# badge.net
KiCad netlist of a schematic drawn in EAGLE
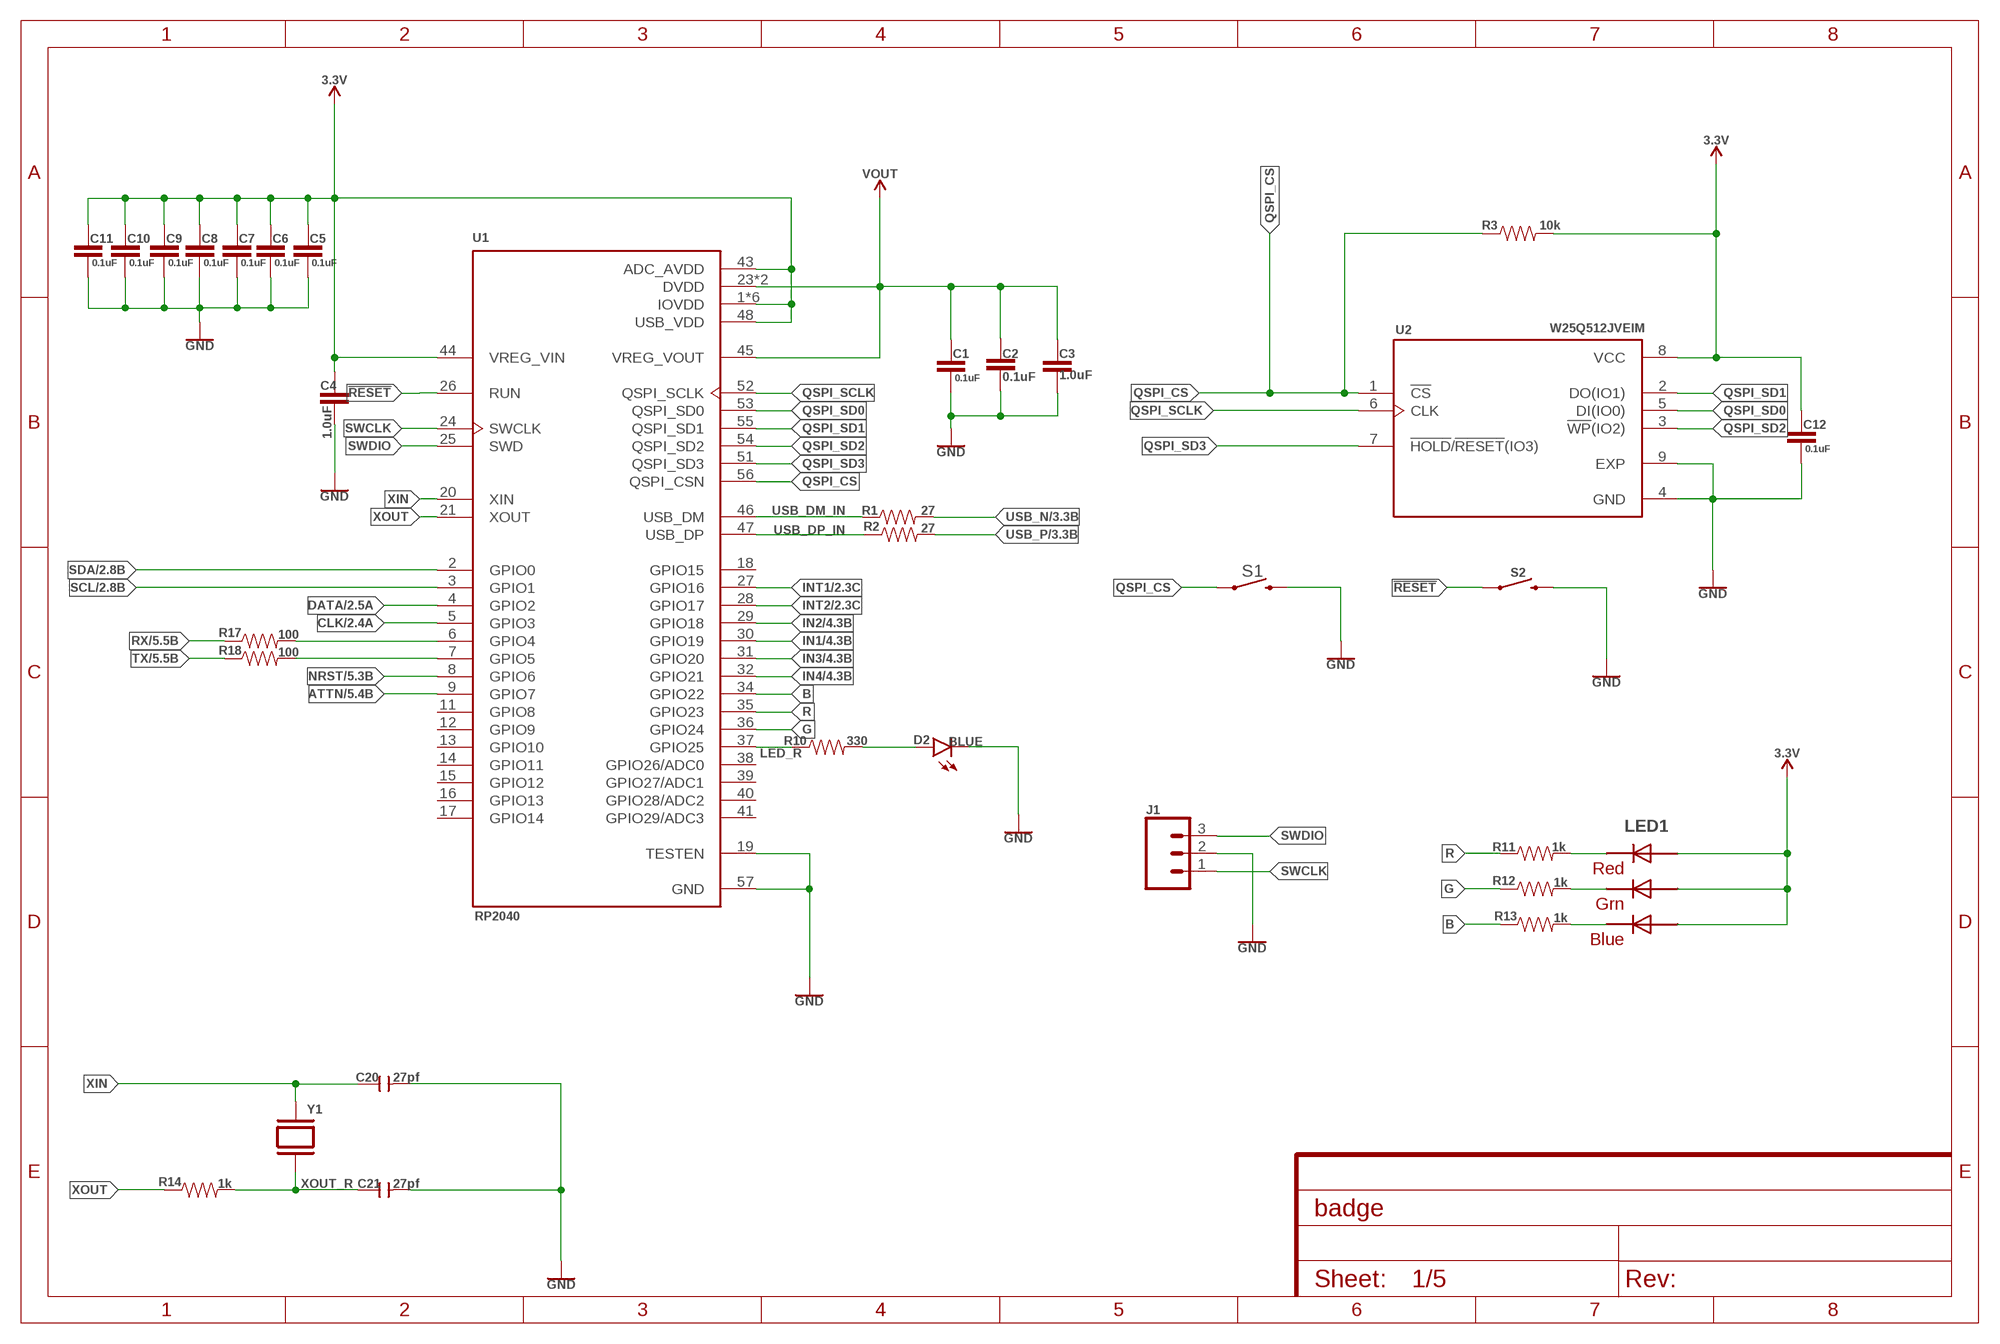
[diagram p0: schematic, sheet 1]
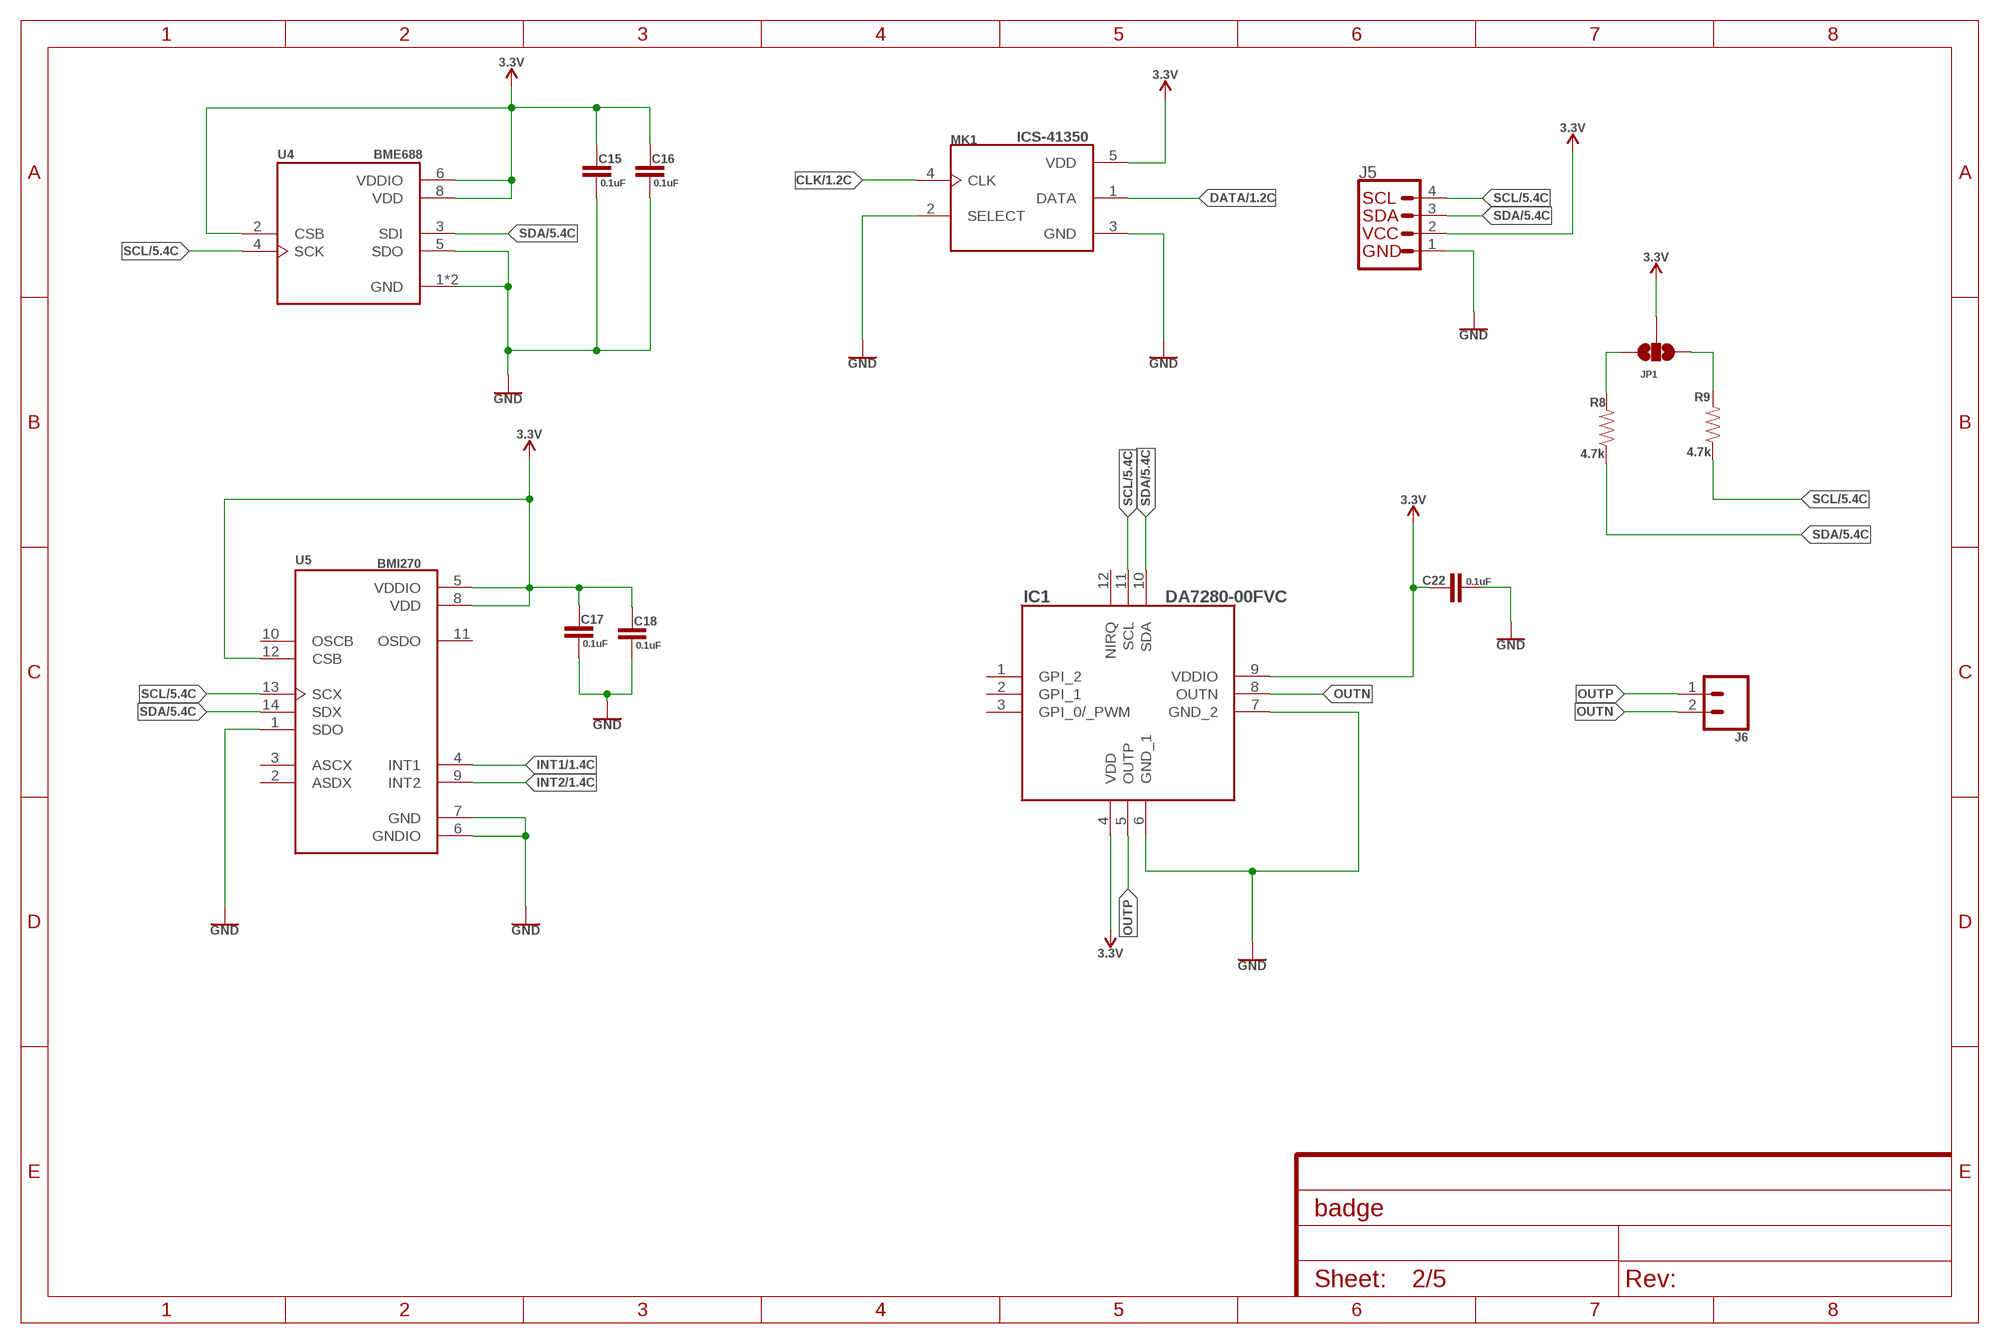
[diagram p1: schematic, sheet 2]
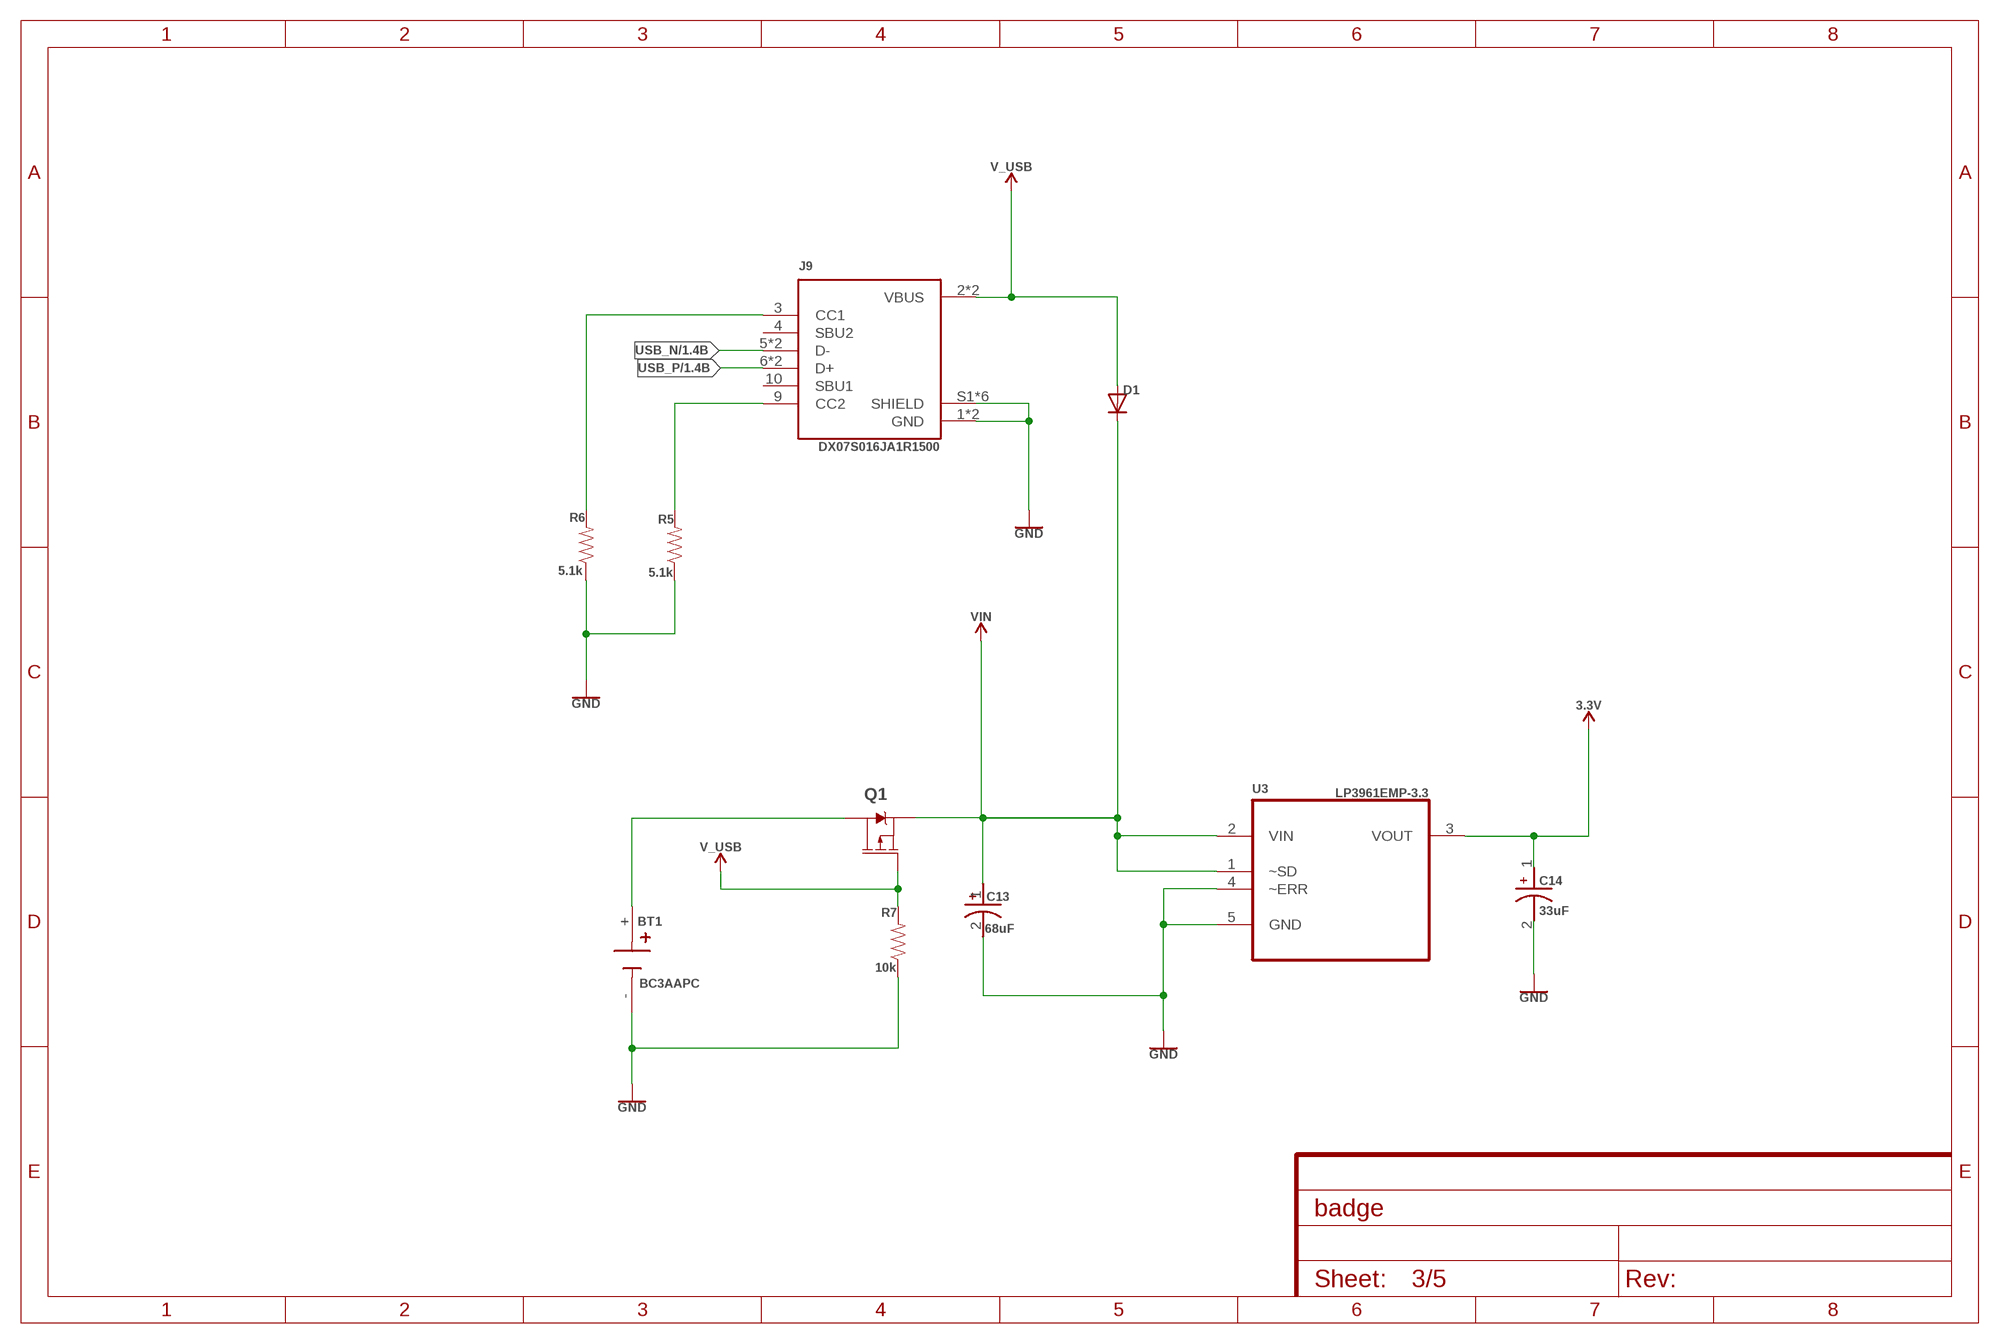
[diagram p2: schematic, sheet 3]
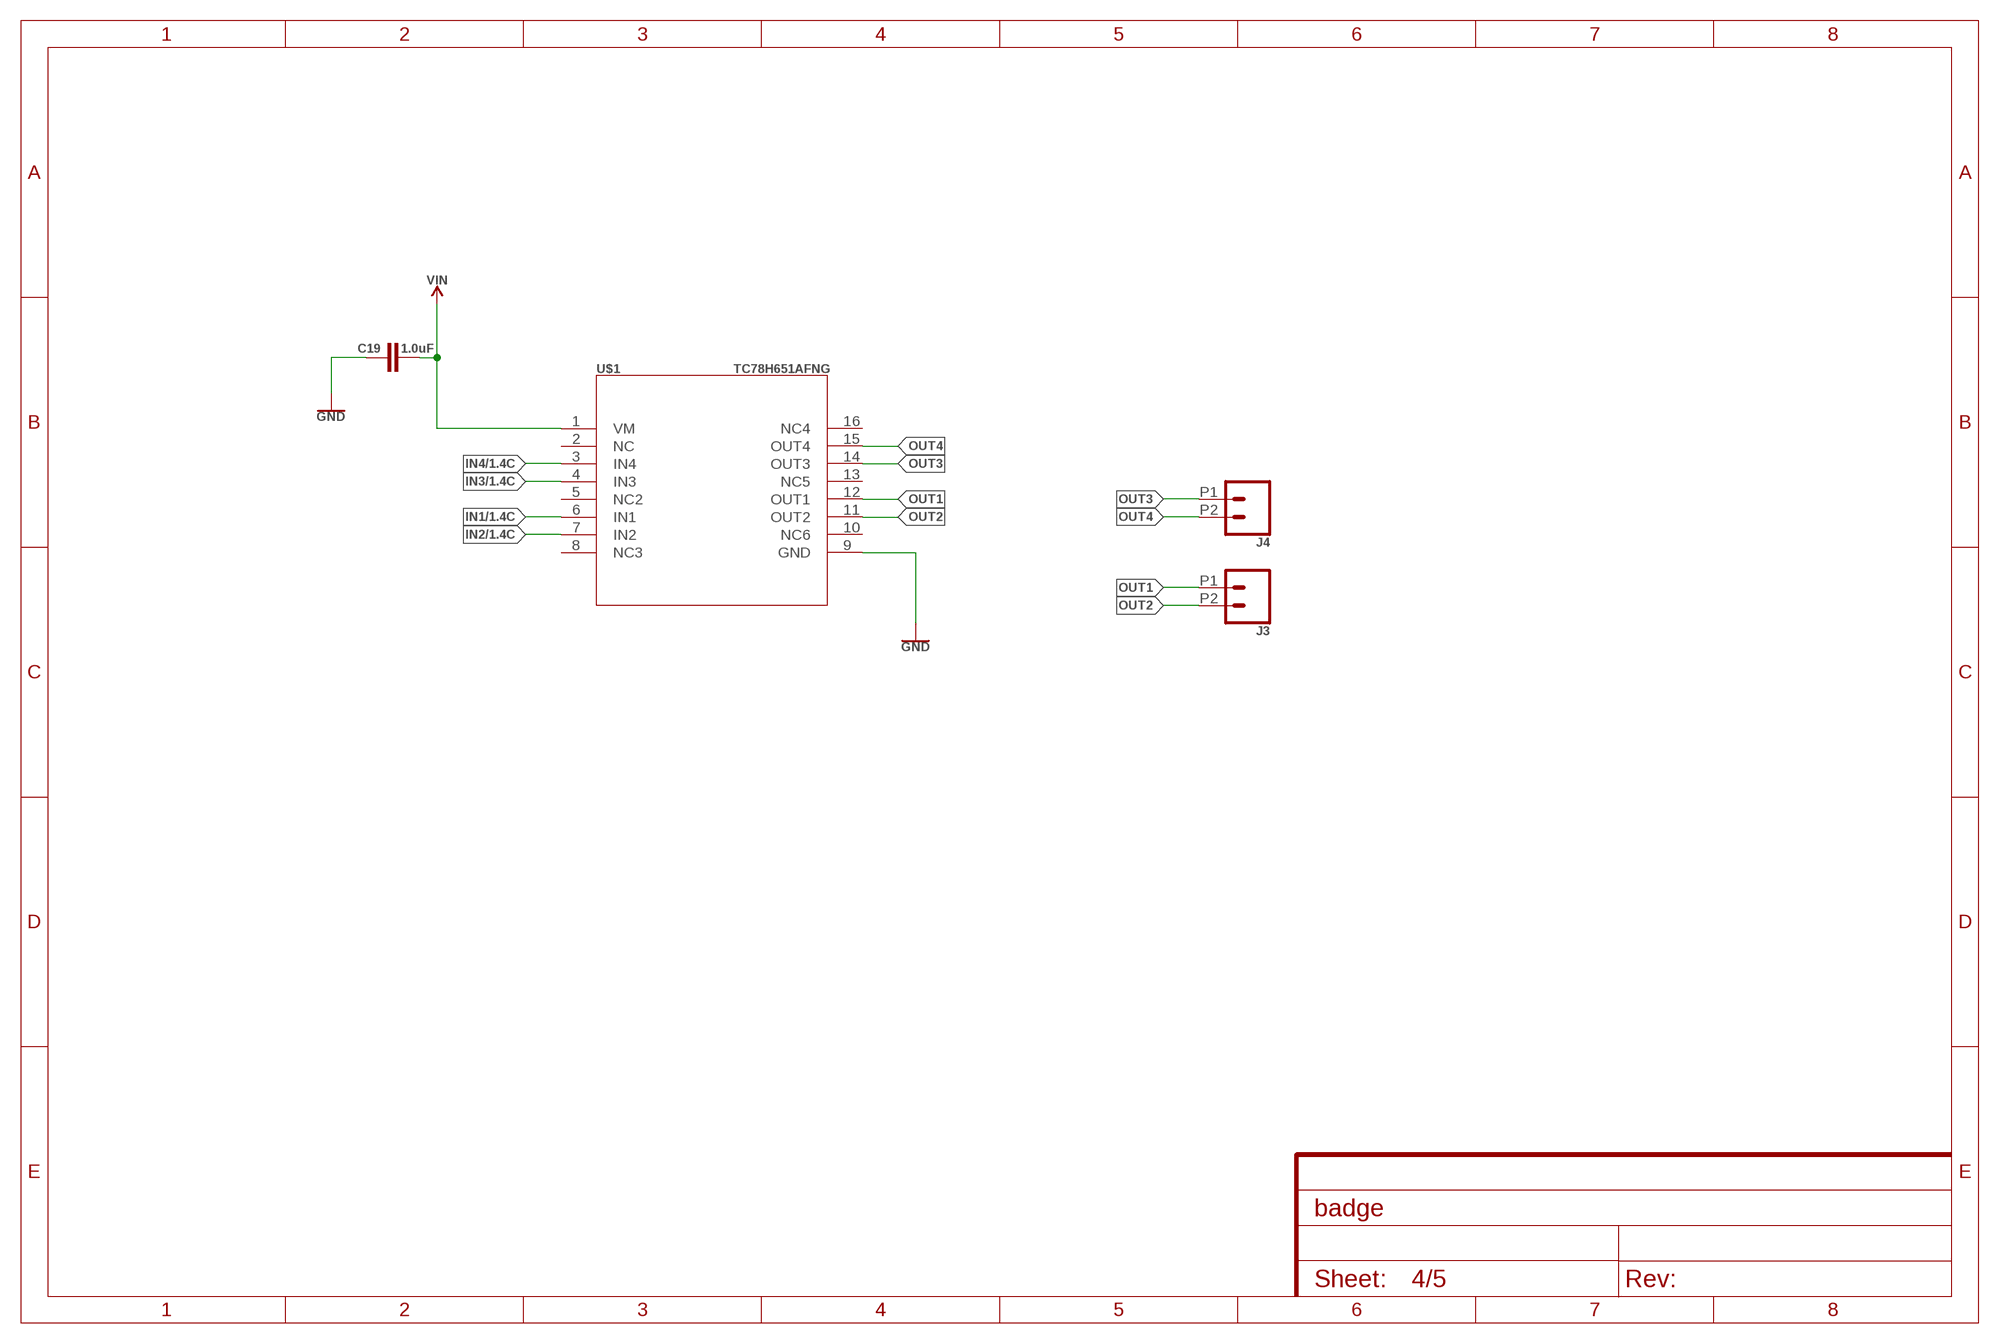
[diagram p3: schematic, sheet 4]
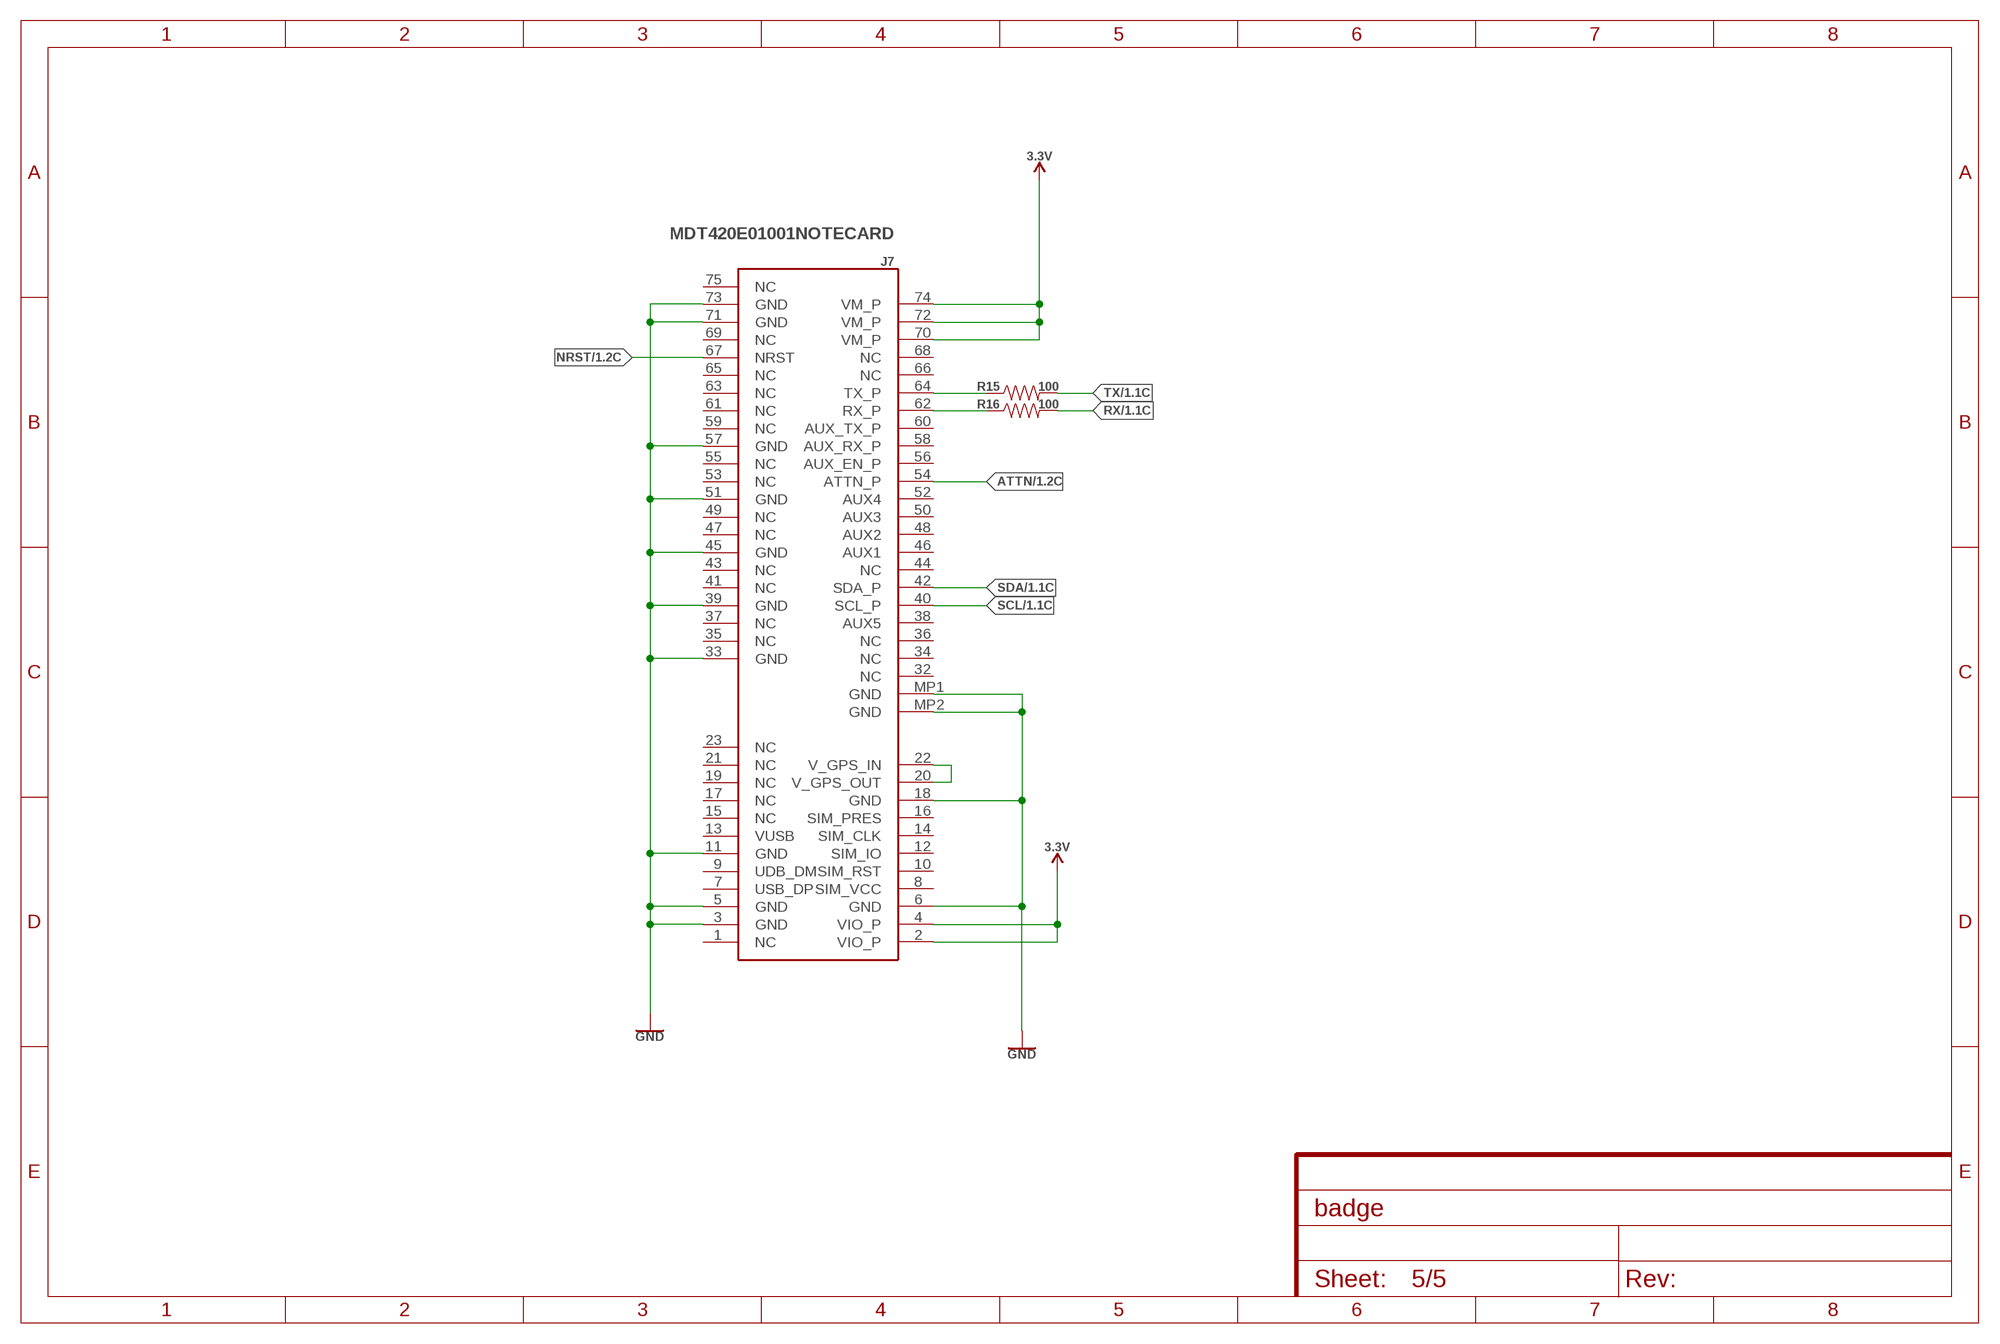
[diagram p4: schematic, sheet 5]

(export (version "E")
  (design (tool "Eeschema 10.0.6"))
  (components
    (comp (ref "BT1")
      (value "BC3AAPC")
      (footprint "eagle-import:BAT_BC3AAPC")
      (fields (field (name "MF") "MPD"))
      (libsource (lib "eagle-import") (part "BC3AAPC"))
    )
    (comp (ref "C13")
      (value "68uF")
      (footprint "eagle-import:CAPMP3216X180N")
      (fields (field (name "MF") "KEMET") (field (name "MP") "T491A686M006AT"))
      (libsource (lib "eagle-import") (part "T491A686M006AT"))
    )
    (comp (ref "C14")
      (value "33uF")
      (footprint "eagle-import:CAPMP3216X180N")
      (fields (field (name "MF") "AVX") (field (name "MP") "TAJA336K006RNJ"))
      (libsource (lib "eagle-import") (part "TAJA336K006RNJ"))
    )
    (comp (ref "D1")
      (value "DIODESOD-123")
      (footprint "eagle-import:SOD-123")
      (libsource (lib "eagle-import") (part "DIODESOD-123"))
    )
    (comp (ref "J9")
      (value "DX07S016JA1R1500")
      (footprint "eagle-import:JAE_DX07S016JA1R1500")
      (fields (field (name "MF") "JAE Electronics"))
      (libsource (lib "eagle-import") (part "DX07S016JA1R1500"))
    )
    (comp (ref "Q1")
      (value "2.5A/30V/105mΩ")
      (footprint "eagle-import:SOT23-3")
      (libsource (lib "eagle-import") (part "MOSFET_PCH-DMG2307L"))
    )
    (comp (ref "R5")
      (value "5.1k")
      (footprint "eagle-import:0603")
      (libsource (lib "eagle-import") (part "5.6KOHM-0603-1/10W-1%"))
    )
    (comp (ref "R6")
      (value "5.1k")
      (footprint "eagle-import:0603")
      (libsource (lib "eagle-import") (part "5.6KOHM-0603-1/10W-1%"))
    )
    (comp (ref "R7")
      (value "10k")
      (footprint "eagle-import:0603")
      (libsource (lib "eagle-import") (part "10KOHM-0603-1/10W-1%"))
    )
    (comp (ref "U3")
      (value "LP3961EMP-3.3")
      (footprint "eagle-import:SOT150P696X180-5N")
      (fields
        (field (name "DIGI-KEY_PART_NUMBER") "LP3961EMP-3.3/NOPBTR-ND")
        (field (name "MF") "Texas Instruments")
        (field (name "MP") "LP3961EMP-3.3/NOPB")
      )
      (libsource (lib "eagle-import") (part "LP3961EMP-3.3"))
    )
    (comp (ref "C1")
      (value "0.1uF")
      (footprint "eagle-import:0603")
      (libsource (lib "eagle-import") (part "0.1UF-0603-25V-(+80/-20%)"))
    )
    (comp (ref "C2")
      (value "0.1uF")
      (footprint "eagle-import:0603")
      (libsource (lib "eagle-import") (part "0.1UF-0603-25V-(+80/-20%)"))
    )
    (comp (ref "C3")
      (value "1.0uF")
      (footprint "eagle-import:0603")
      (libsource (lib "eagle-import") (part "1.0UF-0603-16V-10%"))
    )
    (comp (ref "C4")
      (value "1.0uF")
      (footprint "eagle-import:0603")
      (libsource (lib "eagle-import") (part "1.0UF-0603-16V-10%"))
    )
    (comp (ref "C5")
      (value "0.1uF")
      (footprint "eagle-import:0603")
      (libsource (lib "eagle-import") (part "0.1UF-0603-25V-(+80/-20%)"))
    )
    (comp (ref "C6")
      (value "0.1uF")
      (footprint "eagle-import:0603")
      (libsource (lib "eagle-import") (part "0.1UF-0603-25V-(+80/-20%)"))
    )
    (comp (ref "C7")
      (value "0.1uF")
      (footprint "eagle-import:0603")
      (libsource (lib "eagle-import") (part "0.1UF-0603-25V-(+80/-20%)"))
    )
    (comp (ref "C8")
      (value "0.1uF")
      (footprint "eagle-import:0603")
      (libsource (lib "eagle-import") (part "0.1UF-0603-25V-(+80/-20%)"))
    )
    (comp (ref "C9")
      (value "0.1uF")
      (footprint "eagle-import:0603")
      (libsource (lib "eagle-import") (part "0.1UF-0603-25V-(+80/-20%)"))
    )
    (comp (ref "C10")
      (value "0.1uF")
      (footprint "eagle-import:0603")
      (libsource (lib "eagle-import") (part "0.1UF-0603-25V-(+80/-20%)"))
    )
    (comp (ref "C11")
      (value "0.1uF")
      (footprint "eagle-import:0603")
      (libsource (lib "eagle-import") (part "0.1UF-0603-25V-(+80/-20%)"))
    )
    (comp (ref "C12")
      (value "0.1uF")
      (footprint "eagle-import:0603")
      (libsource (lib "eagle-import") (part "0.1UF-0603-25V-(+80/-20%)"))
    )
    (comp (ref "C20")
      (value "27pf")
      (footprint "eagle-import:C0603")
      (fields (field (name "MPN") "CC0603JRNPO9BN270"))
      (libsource (lib "eagle-import") (part "CERAMIC-27PF-50V-5%-NPO(0603)"))
    )
    (comp (ref "C21")
      (value "27pf")
      (footprint "eagle-import:C0603")
      (fields (field (name "MPN") "CC0603JRNPO9BN270"))
      (libsource (lib "eagle-import") (part "CERAMIC-27PF-50V-5%-NPO(0603)"))
    )
    (comp (ref "D2")
      (value "BLUE")
      (footprint "eagle-import:LED-0603")
      (libsource (lib "eagle-import") (part "LED-BLUE0603"))
    )
    (comp (ref "J1")
      (value "CONN_03LONGPADS")
      (footprint "eagle-import:1X03_LONGPADS")
      (libsource (lib "eagle-import") (part "CONN_03LONGPADS"))
    )
    (comp (ref "LED1")
      (value "RGBLED5050")
      (footprint "eagle-import:RGBLED5050")
      (libsource (lib "eagle-import") (part "RGBLED5050"))
    )
    (comp (ref "R1")
      (value "27")
      (footprint "eagle-import:0603")
      (libsource (lib "eagle-import") (part "27OHM-0603-1/10W-1%"))
    )
    (comp (ref "R2")
      (value "27")
      (footprint "eagle-import:0603")
      (libsource (lib "eagle-import") (part "27OHM-0603-1/10W-1%"))
    )
    (comp (ref "R3")
      (value "10k")
      (footprint "eagle-import:0603")
      (libsource (lib "eagle-import") (part "10KOHM-0603-1/10W-1%"))
    )
    (comp (ref "R10")
      (value "330")
      (footprint "eagle-import:0603")
      (libsource (lib "eagle-import") (part "330OHM-0603-1/10W-1%"))
    )
    (comp (ref "R11")
      (value "1k")
      (footprint "eagle-import:0603")
      (libsource (lib "eagle-import") (part "1KOHM-0603-1/10W-1%"))
    )
    (comp (ref "R12")
      (value "1k")
      (footprint "eagle-import:0603")
      (libsource (lib "eagle-import") (part "1KOHM-0603-1/10W-1%"))
    )
    (comp (ref "R13")
      (value "1k")
      (footprint "eagle-import:0603")
      (libsource (lib "eagle-import") (part "1KOHM-0603-1/10W-1%"))
    )
    (comp (ref "R14")
      (value "1k")
      (footprint "eagle-import:0603")
      (libsource (lib "eagle-import") (part "1KOHM-0603-1/10W-1%"))
    )
    (comp (ref "R17")
      (value "100")
      (footprint "eagle-import:0603")
      (libsource (lib "eagle-import") (part "100OHM-0603-1/4W-5%"))
    )
    (comp (ref "R18")
      (value "100")
      (footprint "eagle-import:0603")
      (libsource (lib "eagle-import") (part "100OHM-0603-1/4W-5%"))
    )
    (comp (ref "S1")
      (value "MOMENTARY-SWITCH-SPST-SMD-6.0X3.5MM")
      (footprint "eagle-import:TACTILE_SWITCH_SMD_6.0X3.5MM")
      (libsource (lib "eagle-import") (part "MOMENTARY-SWITCH-SPST-SMD-6.0X3.5MM"))
    )
    (comp (ref "S2")
      (value "MOMENTARY-SWITCH-SPST-SMD-6.0X3.5MM")
      (footprint "eagle-import:TACTILE_SWITCH_SMD_6.0X3.5MM")
      (libsource (lib "eagle-import") (part "MOMENTARY-SWITCH-SPST-SMD-6.0X3.5MM"))
    )
    (comp (ref "U1")
      (value "RP2040")
      (footprint "eagle-import:QFN40P700X700X90-57N")
      (fields (field (name "MF") "Raspberry Pi"))
      (libsource (lib "eagle-import") (part "RP2040"))
    )
    (comp (ref "U2")
      (value "W25Q512JVEIM")
      (footprint "eagle-import:SON127P600X800X80-9N")
      (fields (field (name "MF") "Winbond Electronics"))
      (libsource (lib "eagle-import") (part "W25Q512JVEIM"))
    )
    (comp (ref "Y1")
      (value "ABLS-12.000MHZ-B4-T")
      (footprint "eagle-import:XTAL_ABLS-12.000MHZ-B4-T")
      (fields (field (name "MF") "Abracon LLC"))
      (libsource (lib "eagle-import") (part "ABLS-12.000MHZ-B4-T"))
    )
    (comp (ref "C15")
      (value "0.1uF")
      (footprint "eagle-import:0603")
      (libsource (lib "eagle-import") (part "0.1UF-0603-25V-(+80/-20%)"))
    )
    (comp (ref "C16")
      (value "0.1uF")
      (footprint "eagle-import:0603")
      (libsource (lib "eagle-import") (part "0.1UF-0603-25V-(+80/-20%)"))
    )
    (comp (ref "C17")
      (value "0.1uF")
      (footprint "eagle-import:0603")
      (libsource (lib "eagle-import") (part "0.1UF-0603-25V-(+80/-20%)"))
    )
    (comp (ref "C18")
      (value "0.1uF")
      (footprint "eagle-import:0603")
      (libsource (lib "eagle-import") (part "0.1UF-0603-25V-(+80/-20%)"))
    )
    (comp (ref "C22")
      (value "0.1uF")
      (footprint "eagle-import:0603")
      (libsource (lib "eagle-import") (part "0.1UF-0603-25V-(+80/-20%)"))
    )
    (comp (ref "IC1")
      (value "DA7280-00FVC")
      (footprint "eagle-import:QFN65P300X300X84-12N")
      (libsource (lib "eagle-import") (part "DA7280-00FVC"))
    )
    (comp (ref "J5")
      (value "QWIIC_CONNECTORJS-1MM")
      (footprint "eagle-import:1X04_1MM_RA")
      (libsource (lib "eagle-import") (part "QWIIC_CONNECTORJS-1MM"))
    )
    (comp (ref "J6")
      (value "CONN_02")
      (footprint "eagle-import:1X02")
      (libsource (lib "eagle-import") (part "SparkFun-Connectors_513_CONN_02"))
    )
    (comp (ref "JP1")
      (value "JUMPER-SMT_3_NO_SILK")
      (footprint "eagle-import:SMT-JUMPER_3_NO_SILK")
      (libsource (lib "eagle-import") (part "JUMPER-SMT_3_NO_SILK"))
    )
    (comp (ref "MK1")
      (value "ICS-41350")
      (footprint "eagle-import:MIC_ICS-41350")
      (fields (field (name "MF") "TDK InvenSense"))
      (libsource (lib "eagle-import") (part "ICS-41350"))
    )
    (comp (ref "R8")
      (value "4.7k")
      (footprint "eagle-import:0603")
      (libsource (lib "eagle-import") (part "4.7KOHM-0603-1/10W-1%"))
    )
    (comp (ref "R9")
      (value "4.7k")
      (footprint "eagle-import:0603")
      (libsource (lib "eagle-import") (part "4.7KOHM-0603-1/10W-1%"))
    )
    (comp (ref "U4")
      (value "BME688")
      (footprint "eagle-import:IC_BME688")
      (fields (field (name "MF") "Bosch Sensortec"))
      (libsource (lib "eagle-import") (part "BME688"))
    )
    (comp (ref "U5")
      (value "BMI270")
      (footprint "eagle-import:XDCR_BMI270")
      (fields (field (name "MF") "Bosch Sensortec"))
      (libsource (lib "eagle-import") (part "BMI270"))
    )
    (comp (ref "C19")
      (value "1.0uF")
      (footprint "eagle-import:0603")
      (libsource (lib "eagle-import") (part "1.0UF-0603-16V-10%"))
    )
    (comp (ref "J3")
      (value "CONN_022.54MM_SCREWTERM")
      (footprint "eagle-import:1X02_2.54_SCREWTERM")
      (libsource (lib "eagle-import") (part "CONN_022.54MM_SCREWTERM"))
    )
    (comp (ref "J4")
      (value "CONN_022.54MM_SCREWTERM")
      (footprint "eagle-import:1X02_2.54_SCREWTERM")
      (libsource (lib "eagle-import") (part "CONN_022.54MM_SCREWTERM"))
    )
    (comp (ref "U$1")
      (value "TC78H651AFNG")
      (footprint "eagle-import:P-TSSOP16-0505-0.65-001")
      (fields (field (name "MF") "Toshiba"))
      (libsource (lib "eagle-import") (part "TC78H651AFNG"))
    )
    (comp (ref "J7")
      (value "MDT420E01001NOTECARD")
      (footprint "eagle-import:NOTECARD")
      (libsource (lib "eagle-import") (part "MDT420E01001NOTECARD"))
    )
    (comp (ref "R15")
      (value "100")
      (footprint "eagle-import:0603")
      (libsource (lib "eagle-import") (part "100OHM-0603-1/4W-5%"))
    )
    (comp (ref "R16")
      (value "100")
      (footprint "eagle-import:0603")
      (libsource (lib "eagle-import") (part "100OHM-0603-1/4W-5%"))
    )
  )
  (nets
    (net (code "1") (name "3.3V") (class "Default")
      (node (ref "C10") (pin "1") (pinfunction "1_1") (pintype "passive"))
      (node (ref "C11") (pin "1") (pinfunction "1_1") (pintype "passive"))
      (node (ref "C12") (pin "1") (pinfunction "1_1") (pintype "passive"))
      (node (ref "C14") (pin "1") (pinfunction "1_1") (pintype "passive"))
      (node (ref "C15") (pin "1") (pinfunction "1_1") (pintype "passive"))
      (node (ref "C16") (pin "1") (pinfunction "1_1") (pintype "passive"))
      (node (ref "C17") (pin "1") (pinfunction "1_1") (pintype "passive"))
      (node (ref "C18") (pin "1") (pinfunction "1_1") (pintype "passive"))
      (node (ref "C22") (pin "1") (pinfunction "1_1") (pintype "passive"))
      (node (ref "C4") (pin "1") (pinfunction "1_1") (pintype "passive"))
      (node (ref "C5") (pin "1") (pinfunction "1_1") (pintype "passive"))
      (node (ref "C6") (pin "1") (pinfunction "1_1") (pintype "passive"))
      (node (ref "C7") (pin "1") (pinfunction "1_1") (pintype "passive"))
      (node (ref "C8") (pin "1") (pinfunction "1_1") (pintype "passive"))
      (node (ref "C9") (pin "1") (pinfunction "1_1") (pintype "passive"))
      (node (ref "IC1") (pin "4") (pinfunction "VDD_4") (pintype "bidirectional"))
      (node (ref "IC1") (pin "9") (pinfunction "VDDIO_9") (pintype "bidirectional"))
      (node (ref "J5") (pin "2") (pinfunction "VCC_2") (pintype "power_in"))
      (node (ref "J7") (pin "2") (pinfunction "VIO_P_2") (pintype "bidirectional"))
      (node (ref "J7") (pin "4") (pinfunction "VIO_P_4") (pintype "bidirectional"))
      (node (ref "J7") (pin "70") (pinfunction "VM_P_70") (pintype "bidirectional"))
      (node (ref "J7") (pin "72") (pinfunction "VM_P_72") (pintype "bidirectional"))
      (node (ref "J7") (pin "74") (pinfunction "VM_P_74") (pintype "bidirectional"))
      (node (ref "JP1") (pin "2") (pinfunction "2_2") (pintype "passive"))
      (node (ref "LED1") (pin "1") (pinfunction "GREEN_A_1") (pintype "bidirectional"))
      (node (ref "LED1") (pin "2") (pinfunction "RED_A_2") (pintype "bidirectional"))
      (node (ref "LED1") (pin "3") (pinfunction "BLUE_A_3") (pintype "bidirectional"))
      (node (ref "MK1") (pin "5") (pinfunction "VDD_5") (pintype "power_in"))
      (node (ref "R3") (pin "2") (pinfunction "2_2") (pintype "passive"))
      (node (ref "U1") (pin "1") (pinfunction "IOVDD_1") (pintype "power_in"))
      (node (ref "U1") (pin "10") (pinfunction "IOVDD_10") (pintype "power_in"))
      (node (ref "U1") (pin "22") (pinfunction "IOVDD_22") (pintype "power_in"))
      (node (ref "U1") (pin "33") (pinfunction "IOVDD_33") (pintype "power_in"))
      (node (ref "U1") (pin "42") (pinfunction "IOVDD_42") (pintype "power_in"))
      (node (ref "U1") (pin "43") (pinfunction "ADC_AVDD_43") (pintype "power_in"))
      (node (ref "U1") (pin "44") (pinfunction "VREG_VIN_44") (pintype "input"))
      (node (ref "U1") (pin "48") (pinfunction "USB_VDD_48") (pintype "power_in"))
      (node (ref "U1") (pin "49") (pinfunction "IOVDD_49") (pintype "power_in"))
      (node (ref "U2") (pin "8") (pinfunction "VCC_8") (pintype "power_in"))
      (node (ref "U3") (pin "3") (pinfunction "VOUT_3") (pintype "output"))
      (node (ref "U4") (pin "2") (pinfunction "CSB_2") (pintype "input"))
      (node (ref "U4") (pin "6") (pinfunction "VDDIO_6") (pintype "power_in"))
      (node (ref "U4") (pin "8") (pinfunction "VDD_8") (pintype "power_in"))
      (node (ref "U5") (pin "12") (pinfunction "CSB_12") (pintype "input"))
      (node (ref "U5") (pin "5") (pinfunction "VDDIO_5") (pintype "power_in"))
      (node (ref "U5") (pin "8") (pinfunction "VDD_8") (pintype "power_in"))
    )
    (net (code "2") (name "ATTN") (class "Default")
      (node (ref "J7") (pin "54") (pinfunction "ATTN_P_54") (pintype "bidirectional"))
      (node (ref "U1") (pin "9") (pinfunction "GPIO7_9") (pintype "bidirectional"))
    )
    (net (code "3") (name "B") (class "Default")
      (node (ref "R13") (pin "1") (pinfunction "1_1") (pintype "passive"))
      (node (ref "U1") (pin "34") (pinfunction "GPIO22_34") (pintype "bidirectional"))
    )
    (net (code "4") (name "CLK") (class "Default")
      (node (ref "MK1") (pin "4") (pinfunction "CLK_4") (pintype "input"))
      (node (ref "U1") (pin "5") (pinfunction "GPIO3_5") (pintype "bidirectional"))
    )
    (net (code "5") (name "DATA") (class "Default")
      (node (ref "MK1") (pin "1") (pinfunction "DATA_1") (pintype "output"))
      (node (ref "U1") (pin "4") (pinfunction "GPIO2_4") (pintype "bidirectional"))
    )
    (net (code "6") (name "G") (class "Default")
      (node (ref "R12") (pin "1") (pinfunction "1_1") (pintype "passive"))
      (node (ref "U1") (pin "36") (pinfunction "GPIO24_36") (pintype "bidirectional"))
    )
    (net (code "7") (name "GND") (class "Default")
      (node (ref "BT1") (pin "-") (pinfunction "-_-") (pintype "passive"))
      (node (ref "C1") (pin "2") (pinfunction "2_2") (pintype "passive"))
      (node (ref "C10") (pin "2") (pinfunction "2_2") (pintype "passive"))
      (node (ref "C11") (pin "2") (pinfunction "2_2") (pintype "passive"))
      (node (ref "C12") (pin "2") (pinfunction "2_2") (pintype "passive"))
      (node (ref "C13") (pin "2") (pinfunction "2_2") (pintype "passive"))
      (node (ref "C14") (pin "2") (pinfunction "2_2") (pintype "passive"))
      (node (ref "C15") (pin "2") (pinfunction "2_2") (pintype "passive"))
      (node (ref "C16") (pin "2") (pinfunction "2_2") (pintype "passive"))
      (node (ref "C17") (pin "2") (pinfunction "2_2") (pintype "passive"))
      (node (ref "C18") (pin "2") (pinfunction "2_2") (pintype "passive"))
      (node (ref "C19") (pin "1") (pinfunction "1_1") (pintype "passive"))
      (node (ref "C2") (pin "2") (pinfunction "2_2") (pintype "passive"))
      (node (ref "C20") (pin "2") (pinfunction "2_2") (pintype "passive"))
      (node (ref "C21") (pin "2") (pinfunction "2_2") (pintype "passive"))
      (node (ref "C22") (pin "2") (pinfunction "2_2") (pintype "passive"))
      (node (ref "C3") (pin "2") (pinfunction "2_2") (pintype "passive"))
      (node (ref "C4") (pin "2") (pinfunction "2_2") (pintype "passive"))
      (node (ref "C5") (pin "2") (pinfunction "2_2") (pintype "passive"))
      (node (ref "C6") (pin "2") (pinfunction "2_2") (pintype "passive"))
      (node (ref "C7") (pin "2") (pinfunction "2_2") (pintype "passive"))
      (node (ref "C8") (pin "2") (pinfunction "2_2") (pintype "passive"))
      (node (ref "C9") (pin "2") (pinfunction "2_2") (pintype "passive"))
      (node (ref "D2") (pin "C") (pinfunction "C_C") (pintype "passive"))
      (node (ref "IC1") (pin "6") (pinfunction "GND_1_6") (pintype "bidirectional"))
      (node (ref "IC1") (pin "7") (pinfunction "GND_2_7") (pintype "bidirectional"))
      (node (ref "J1") (pin "2") (pinfunction "2_2") (pintype "passive"))
      (node (ref "J5") (pin "1") (pinfunction "GND_1") (pintype "power_in"))
      (node (ref "J7") (pin "11") (pinfunction "GND_11") (pintype "bidirectional"))
      (node (ref "J7") (pin "18") (pinfunction "GND_18") (pintype "bidirectional"))
      (node (ref "J7") (pin "3") (pinfunction "GND_3") (pintype "bidirectional"))
      (node (ref "J7") (pin "33") (pinfunction "GND_33") (pintype "bidirectional"))
      (node (ref "J7") (pin "39") (pinfunction "GND_39") (pintype "bidirectional"))
      (node (ref "J7") (pin "45") (pinfunction "GND_45") (pintype "bidirectional"))
      (node (ref "J7") (pin "5") (pinfunction "GND_5") (pintype "bidirectional"))
      (node (ref "J7") (pin "51") (pinfunction "GND_51") (pintype "bidirectional"))
      (node (ref "J7") (pin "57") (pinfunction "GND_57") (pintype "bidirectional"))
      (node (ref "J7") (pin "6") (pinfunction "GND_6") (pintype "bidirectional"))
      (node (ref "J7") (pin "71") (pinfunction "GND_71") (pintype "bidirectional"))
      (node (ref "J7") (pin "73") (pinfunction "GND_73") (pintype "bidirectional"))
      (node (ref "J7") (pin "MP1") (pinfunction "GND_MP1") (pintype "power_in"))
      (node (ref "J7") (pin "MP2") (pinfunction "GND_MP2") (pintype "bidirectional"))
      (node (ref "J9") (pin "1") (pinfunction "GND_1") (pintype "power_in"))
      (node (ref "J9") (pin "12") (pinfunction "GND_12") (pintype "power_in"))
      (node (ref "J9") (pin "S1") (pinfunction "SHIELD_S1") (pintype "passive"))
      (node (ref "J9") (pin "S2") (pinfunction "SHIELD_S2") (pintype "passive"))
      (node (ref "J9") (pin "S3") (pinfunction "SHIELD_S3") (pintype "passive"))
      (node (ref "J9") (pin "S4") (pinfunction "SHIELD_S4") (pintype "passive"))
      (node (ref "J9") (pin "S5") (pinfunction "SHIELD_S5") (pintype "passive"))
      (node (ref "J9") (pin "S6") (pinfunction "SHIELD_S6") (pintype "passive"))
      (node (ref "MK1") (pin "2") (pinfunction "SELECT_2") (pintype "input"))
      (node (ref "MK1") (pin "3") (pinfunction "GND_3") (pintype "power_in"))
      (node (ref "R5") (pin "1") (pinfunction "1_1") (pintype "passive"))
      (node (ref "R6") (pin "1") (pinfunction "1_1") (pintype "passive"))
      (node (ref "R7") (pin "1") (pinfunction "1_1") (pintype "passive"))
      (node (ref "S1") (pin "2") (pinfunction "2_2") (pintype "passive"))
      (node (ref "S2") (pin "2") (pinfunction "2_2") (pintype "passive"))
      (node (ref "U$1") (pin "9") (pinfunction "GND_9") (pintype "bidirectional"))
      (node (ref "U1") (pin "19") (pinfunction "TESTEN_19") (pintype "passive"))
      (node (ref "U1") (pin "57") (pinfunction "GND_57") (pintype "power_in"))
      (node (ref "U2") (pin "4") (pinfunction "GND_4") (pintype "power_in"))
      (node (ref "U2") (pin "9") (pinfunction "EXP_9") (pintype "passive"))
      (node (ref "U3") (pin "4") (pinfunction "~{ERR}_4") (pintype "passive"))
      (node (ref "U3") (pin "5") (pinfunction "GND_5") (pintype "passive"))
      (node (ref "U4") (pin "1") (pinfunction "GND_1") (pintype "power_in"))
      (node (ref "U4") (pin "5") (pinfunction "SDO_5") (pintype "bidirectional"))
      (node (ref "U4") (pin "7") (pinfunction "GND_7") (pintype "power_in"))
      (node (ref "U5") (pin "1") (pinfunction "SDO_1") (pintype "bidirectional"))
      (node (ref "U5") (pin "6") (pinfunction "GNDIO_6") (pintype "power_in"))
      (node (ref "U5") (pin "7") (pinfunction "GND_7") (pintype "power_in"))
    )
    (net (code "8") (name "IN1") (class "Default")
      (node (ref "U$1") (pin "6") (pinfunction "IN1_6") (pintype "bidirectional"))
      (node (ref "U1") (pin "30") (pinfunction "GPIO19_30") (pintype "bidirectional"))
    )
    (net (code "9") (name "IN2") (class "Default")
      (node (ref "U$1") (pin "7") (pinfunction "IN2_7") (pintype "bidirectional"))
      (node (ref "U1") (pin "29") (pinfunction "GPIO18_29") (pintype "bidirectional"))
    )
    (net (code "10") (name "IN3") (class "Default")
      (node (ref "U$1") (pin "4") (pinfunction "IN3_4") (pintype "bidirectional"))
      (node (ref "U1") (pin "31") (pinfunction "GPIO20_31") (pintype "bidirectional"))
    )
    (net (code "11") (name "IN4") (class "Default")
      (node (ref "U$1") (pin "3") (pinfunction "IN4_3") (pintype "bidirectional"))
      (node (ref "U1") (pin "32") (pinfunction "GPIO21_32") (pintype "bidirectional"))
    )
    (net (code "12") (name "INT1") (class "Default")
      (node (ref "U1") (pin "27") (pinfunction "GPIO16_27") (pintype "bidirectional"))
      (node (ref "U5") (pin "4") (pinfunction "INT1_4") (pintype "bidirectional"))
    )
    (net (code "13") (name "INT2") (class "Default")
      (node (ref "U1") (pin "28") (pinfunction "GPIO17_28") (pintype "bidirectional"))
      (node (ref "U5") (pin "9") (pinfunction "INT2_9") (pintype "bidirectional"))
    )
    (net (code "14") (name "LED_R") (class "Default")
      (node (ref "R10") (pin "1") (pinfunction "1_1") (pintype "passive"))
      (node (ref "U1") (pin "37") (pinfunction "GPIO25_37") (pintype "bidirectional"))
    )
    (net (code "15") (name "NRST") (class "Default")
      (node (ref "J7") (pin "67") (pinfunction "NRST_67") (pintype "bidirectional"))
      (node (ref "U1") (pin "8") (pinfunction "GPIO6_8") (pintype "bidirectional"))
    )
    (net (code "16") (name "Net-(D2-PadA)") (class "Default")
      (node (ref "D2") (pin "A") (pinfunction "A_A") (pintype "passive"))
      (node (ref "R10") (pin "2") (pinfunction "2_2") (pintype "passive"))
    )
    (net (code "17") (name "Net-(J7-RX_P)") (class "Default")
      (node (ref "J7") (pin "62") (pinfunction "RX_P_62") (pintype "bidirectional"))
      (node (ref "R16") (pin "1") (pinfunction "1_1") (pintype "passive"))
    )
    (net (code "18") (name "Net-(J7-TX_P)") (class "Default")
      (node (ref "J7") (pin "64") (pinfunction "TX_P_64") (pintype "bidirectional"))
      (node (ref "R15") (pin "1") (pinfunction "1_1") (pintype "passive"))
    )
    (net (code "19") (name "Net-(J7-V_GPS_IN)") (class "Default")
      (node (ref "J7") (pin "20") (pinfunction "V_GPS_OUT_20") (pintype "bidirectional"))
      (node (ref "J7") (pin "22") (pinfunction "V_GPS_IN_22") (pintype "bidirectional"))
    )
    (net (code "20") (name "Net-(J9-CC1)") (class "Default")
      (node (ref "J9") (pin "3") (pinfunction "CC1_3") (pintype "passive"))
      (node (ref "R6") (pin "2") (pinfunction "2_2") (pintype "passive"))
    )
    (net (code "21") (name "Net-(J9-CC2)") (class "Default")
      (node (ref "J9") (pin "9") (pinfunction "CC2_9") (pintype "passive"))
      (node (ref "R5") (pin "2") (pinfunction "2_2") (pintype "passive"))
    )
    (net (code "22") (name "Net-(JP1-Pad1)") (class "Default")
      (node (ref "JP1") (pin "1") (pinfunction "1_1") (pintype "passive"))
      (node (ref "R9") (pin "2") (pinfunction "2_2") (pintype "passive"))
    )
    (net (code "23") (name "Net-(JP1-Pad3)") (class "Default")
      (node (ref "JP1") (pin "3") (pinfunction "3_3") (pintype "passive"))
      (node (ref "R8") (pin "2") (pinfunction "2_2") (pintype "passive"))
    )
    (net (code "24") (name "Net-(LED1-BLUE_C)") (class "Default")
      (node (ref "LED1") (pin "4") (pinfunction "BLUE_C_4") (pintype "bidirectional"))
      (node (ref "R13") (pin "2") (pinfunction "2_2") (pintype "passive"))
    )
    (net (code "25") (name "Net-(LED1-GREEN_C)") (class "Default")
      (node (ref "LED1") (pin "6") (pinfunction "GREEN_C_6") (pintype "bidirectional"))
      (node (ref "R12") (pin "2") (pinfunction "2_2") (pintype "passive"))
    )
    (net (code "26") (name "Net-(LED1-RED_C)") (class "Default")
      (node (ref "LED1") (pin "5") (pinfunction "RED_C_5") (pintype "bidirectional"))
      (node (ref "R11") (pin "2") (pinfunction "2_2") (pintype "passive"))
    )
    (net (code "27") (name "Net-(Q1-D)") (class "Default")
      (node (ref "BT1") (pin "+") (pinfunction "+_+") (pintype "passive"))
      (node (ref "Q1") (pin "3") (pinfunction "D_3") (pintype "bidirectional"))
    )
    (net (code "28") (name "Net-(U1-GPIO4)") (class "Default")
      (node (ref "R17") (pin "2") (pinfunction "2_2") (pintype "passive"))
      (node (ref "U1") (pin "6") (pinfunction "GPIO4_6") (pintype "bidirectional"))
    )
    (net (code "29") (name "Net-(U1-GPIO5)") (class "Default")
      (node (ref "R18") (pin "2") (pinfunction "2_2") (pintype "passive"))
      (node (ref "U1") (pin "7") (pinfunction "GPIO5_7") (pintype "bidirectional"))
    )
    (net (code "30") (name "OUT1") (class "Default")
      (node (ref "J3") (pin "P1") (pinfunction "1_P1") (pintype "passive"))
      (node (ref "U$1") (pin "12") (pinfunction "OUT1_12") (pintype "bidirectional"))
    )
    (net (code "31") (name "OUT2") (class "Default")
      (node (ref "J3") (pin "P2") (pinfunction "2_P2") (pintype "passive"))
      (node (ref "U$1") (pin "11") (pinfunction "OUT2_11") (pintype "bidirectional"))
    )
    (net (code "32") (name "OUT3") (class "Default")
      (node (ref "J4") (pin "P1") (pinfunction "1_P1") (pintype "passive"))
      (node (ref "U$1") (pin "14") (pinfunction "OUT3_14") (pintype "bidirectional"))
    )
    (net (code "33") (name "OUT4") (class "Default")
      (node (ref "J4") (pin "P2") (pinfunction "2_P2") (pintype "passive"))
      (node (ref "U$1") (pin "15") (pinfunction "OUT4_15") (pintype "bidirectional"))
    )
    (net (code "34") (name "OUTN") (class "Default")
      (node (ref "IC1") (pin "8") (pinfunction "OUTN_8") (pintype "bidirectional"))
      (node (ref "J6") (pin "2") (pinfunction "2_2") (pintype "passive"))
    )
    (net (code "35") (name "OUTP") (class "Default")
      (node (ref "IC1") (pin "5") (pinfunction "OUTP_5") (pintype "bidirectional"))
      (node (ref "J6") (pin "1") (pinfunction "1_1") (pintype "passive"))
    )
    (net (code "36") (name "QSPI_CS") (class "Default")
      (node (ref "R3") (pin "1") (pinfunction "1_1") (pintype "passive"))
      (node (ref "S1") (pin "1") (pinfunction "1_1") (pintype "passive"))
      (node (ref "U1") (pin "56") (pinfunction "QSPI_CSN_56") (pintype "bidirectional"))
      (node (ref "U2") (pin "1") (pinfunction "~{CS}_1") (pintype "input"))
    )
    (net (code "37") (name "QSPI_SCLK") (class "Default")
      (node (ref "U1") (pin "52") (pinfunction "QSPI_SCLK_52") (pintype "bidirectional"))
      (node (ref "U2") (pin "6") (pinfunction "CLK_6") (pintype "input"))
    )
    (net (code "38") (name "QSPI_SD0") (class "Default")
      (node (ref "U1") (pin "53") (pinfunction "QSPI_SD0_53") (pintype "bidirectional"))
      (node (ref "U2") (pin "5") (pinfunction "DI(IO0)_5") (pintype "bidirectional"))
    )
    (net (code "39") (name "QSPI_SD1") (class "Default")
      (node (ref "U1") (pin "55") (pinfunction "QSPI_SD1_55") (pintype "bidirectional"))
      (node (ref "U2") (pin "2") (pinfunction "DO(IO1)_2") (pintype "bidirectional"))
    )
    (net (code "40") (name "QSPI_SD2") (class "Default")
      (node (ref "U1") (pin "54") (pinfunction "QSPI_SD2_54") (pintype "bidirectional"))
      (node (ref "U2") (pin "3") (pinfunction "~{WP}(IO2)_3") (pintype "bidirectional"))
    )
    (net (code "41") (name "QSPI_SD3") (class "Default")
      (node (ref "U1") (pin "51") (pinfunction "QSPI_SD3_51") (pintype "bidirectional"))
      (node (ref "U2") (pin "7") (pinfunction "~{HOLD}/~{RESET}(IO3)_7") (pintype "bidirectional"))
    )
    (net (code "42") (name "R") (class "Default")
      (node (ref "R11") (pin "1") (pinfunction "1_1") (pintype "passive"))
      (node (ref "U1") (pin "35") (pinfunction "GPIO23_35") (pintype "bidirectional"))
    )
    (net (code "43") (name "RX") (class "Default")
      (node (ref "R16") (pin "2") (pinfunction "2_2") (pintype "passive"))
      (node (ref "R17") (pin "1") (pinfunction "1_1") (pintype "passive"))
    )
    (net (code "44") (name "SCL") (class "Default")
      (node (ref "IC1") (pin "11") (pinfunction "SCL_11") (pintype "bidirectional"))
      (node (ref "J5") (pin "4") (pinfunction "SCL_4") (pintype "passive"))
      (node (ref "J7") (pin "40") (pinfunction "SCL_P_40") (pintype "bidirectional"))
      (node (ref "R9") (pin "1") (pinfunction "1_1") (pintype "passive"))
      (node (ref "U1") (pin "3") (pinfunction "GPIO1_3") (pintype "bidirectional"))
      (node (ref "U4") (pin "4") (pinfunction "SCK_4") (pintype "input"))
      (node (ref "U5") (pin "13") (pinfunction "SCX_13") (pintype "input"))
    )
    (net (code "45") (name "SDA") (class "Default")
      (node (ref "IC1") (pin "10") (pinfunction "SDA_10") (pintype "bidirectional"))
      (node (ref "J5") (pin "3") (pinfunction "SDA_3") (pintype "passive"))
      (node (ref "J7") (pin "42") (pinfunction "SDA_P_42") (pintype "bidirectional"))
      (node (ref "R8") (pin "1") (pinfunction "1_1") (pintype "passive"))
      (node (ref "U1") (pin "2") (pinfunction "GPIO0_2") (pintype "bidirectional"))
      (node (ref "U4") (pin "3") (pinfunction "SDI_3") (pintype "bidirectional"))
      (node (ref "U5") (pin "14") (pinfunction "SDX_14") (pintype "bidirectional"))
    )
    (net (code "46") (name "SWCLK") (class "Default")
      (node (ref "J1") (pin "1") (pinfunction "1_1") (pintype "passive"))
      (node (ref "U1") (pin "24") (pinfunction "SWCLK_24") (pintype "input"))
    )
    (net (code "47") (name "SWDIO") (class "Default")
      (node (ref "J1") (pin "3") (pinfunction "3_3") (pintype "passive"))
      (node (ref "U1") (pin "25") (pinfunction "SWD_25") (pintype "bidirectional"))
    )
    (net (code "48") (name "TX") (class "Default")
      (node (ref "R15") (pin "2") (pinfunction "2_2") (pintype "passive"))
      (node (ref "R18") (pin "1") (pinfunction "1_1") (pintype "passive"))
    )
    (net (code "49") (name "USB_DM_IN") (class "Default")
      (node (ref "R1") (pin "1") (pinfunction "1_1") (pintype "passive"))
      (node (ref "U1") (pin "46") (pinfunction "USB_DM_46") (pintype "bidirectional"))
    )
    (net (code "50") (name "USB_DP_IN") (class "Default")
      (node (ref "R2") (pin "1") (pinfunction "1_1") (pintype "passive"))
      (node (ref "U1") (pin "47") (pinfunction "USB_DP_47") (pintype "bidirectional"))
    )
    (net (code "51") (name "USB_N") (class "Default")
      (node (ref "J9") (pin "5") (pinfunction "D-_5") (pintype "passive"))
      (node (ref "J9") (pin "8") (pinfunction "D-_8") (pintype "passive"))
      (node (ref "R1") (pin "2") (pinfunction "2_2") (pintype "passive"))
    )
    (net (code "52") (name "USB_P") (class "Default")
      (node (ref "J9") (pin "6") (pinfunction "D+_6") (pintype "passive"))
      (node (ref "J9") (pin "7") (pinfunction "D+_7") (pintype "passive"))
      (node (ref "R2") (pin "2") (pinfunction "2_2") (pintype "passive"))
    )
    (net (code "53") (name "VIN") (class "Default")
      (node (ref "C13") (pin "1") (pinfunction "1_1") (pintype "passive"))
      (node (ref "C19") (pin "2") (pinfunction "2_2") (pintype "passive"))
      (node (ref "D1") (pin "C") (pinfunction "C_C") (pintype "passive"))
      (node (ref "Q1") (pin "2") (pinfunction "S_2") (pintype "bidirectional"))
      (node (ref "U$1") (pin "1") (pinfunction "VM_1") (pintype "bidirectional"))
      (node (ref "U3") (pin "1") (pinfunction "~{SD}_1") (pintype "passive"))
      (node (ref "U3") (pin "2") (pinfunction "VIN_2") (pintype "power_in"))
    )
    (net (code "54") (name "VOUT") (class "Default")
      (node (ref "C1") (pin "1") (pinfunction "1_1") (pintype "passive"))
      (node (ref "C2") (pin "1") (pinfunction "1_1") (pintype "passive"))
      (node (ref "C3") (pin "1") (pinfunction "1_1") (pintype "passive"))
      (node (ref "U1") (pin "23") (pinfunction "DVDD_23") (pintype "power_in"))
      (node (ref "U1") (pin "45") (pinfunction "VREG_VOUT_45") (pintype "output"))
      (node (ref "U1") (pin "50") (pinfunction "DVDD_50") (pintype "power_in"))
    )
    (net (code "55") (name "V_USB") (class "Default")
      (node (ref "D1") (pin "A") (pinfunction "A_A") (pintype "passive"))
      (node (ref "J9") (pin "11") (pinfunction "VBUS_11") (pintype "power_in"))
      (node (ref "J9") (pin "2") (pinfunction "VBUS_2") (pintype "power_in"))
      (node (ref "Q1") (pin "1") (pinfunction "G_1") (pintype "bidirectional"))
      (node (ref "R7") (pin "2") (pinfunction "2_2") (pintype "passive"))
    )
    (net (code "56") (name "XIN") (class "Default")
      (node (ref "C20") (pin "1") (pinfunction "1_1") (pintype "passive"))
      (node (ref "U1") (pin "20") (pinfunction "XIN_20") (pintype "input"))
      (node (ref "Y1") (pin "2") (pinfunction "2_2") (pintype "passive"))
    )
    (net (code "57") (name "XOUT") (class "Default")
      (node (ref "R14") (pin "1") (pinfunction "1_1") (pintype "passive"))
      (node (ref "U1") (pin "21") (pinfunction "XOUT_21") (pintype "output"))
    )
    (net (code "58") (name "XOUT_R") (class "Default")
      (node (ref "C21") (pin "1") (pinfunction "1_1") (pintype "passive"))
      (node (ref "R14") (pin "2") (pinfunction "2_2") (pintype "passive"))
      (node (ref "Y1") (pin "1") (pinfunction "1_1") (pintype "passive"))
    )
    (net (code "59") (name "unconnected-(IC1-GPI_0{slash}_PWM-Pad3)") (class "Default")
      (node (ref "IC1") (pin "3") (pinfunction "GPI_0/_PWM_3") (pintype "bidirectional"))
    )
    (net (code "60") (name "unconnected-(IC1-GPI_1-Pad2)") (class "Default")
      (node (ref "IC1") (pin "2") (pinfunction "GPI_1_2") (pintype "bidirectional"))
    )
    (net (code "61") (name "unconnected-(IC1-GPI_2-Pad1)") (class "Default")
      (node (ref "IC1") (pin "1") (pinfunction "GPI_2_1") (pintype "bidirectional"))
    )
    (net (code "62") (name "unconnected-(IC1-NIRQ-Pad12)") (class "Default")
      (node (ref "IC1") (pin "12") (pinfunction "NIRQ_12") (pintype "bidirectional"))
    )
    (net (code "63") (name "unconnected-(J7-AUX1-Pad46)") (class "Default")
      (node (ref "J7") (pin "46") (pinfunction "AUX1_46") (pintype "bidirectional"))
    )
    (net (code "64") (name "unconnected-(J7-AUX2-Pad48)") (class "Default")
      (node (ref "J7") (pin "48") (pinfunction "AUX2_48") (pintype "bidirectional"))
    )
    (net (code "65") (name "unconnected-(J7-AUX3-Pad50)") (class "Default")
      (node (ref "J7") (pin "50") (pinfunction "AUX3_50") (pintype "bidirectional"))
    )
    (net (code "66") (name "unconnected-(J7-AUX4-Pad52)") (class "Default")
      (node (ref "J7") (pin "52") (pinfunction "AUX4_52") (pintype "bidirectional"))
    )
    (net (code "67") (name "unconnected-(J7-AUX5-Pad38)") (class "Default")
      (node (ref "J7") (pin "38") (pinfunction "AUX5_38") (pintype "bidirectional"))
    )
    (net (code "68") (name "unconnected-(J7-AUX_EN_P-Pad56)") (class "Default")
      (node (ref "J7") (pin "56") (pinfunction "AUX_EN_P_56") (pintype "bidirectional"))
    )
    (net (code "69") (name "unconnected-(J7-AUX_RX_P-Pad58)") (class "Default")
      (node (ref "J7") (pin "58") (pinfunction "AUX_RX_P_58") (pintype "bidirectional"))
    )
    (net (code "70") (name "unconnected-(J7-AUX_TX_P-Pad60)") (class "Default")
      (node (ref "J7") (pin "60") (pinfunction "AUX_TX_P_60") (pintype "bidirectional"))
    )
    (net (code "71") (name "unconnected-(J7-NC-Pad1)") (class "Default")
      (node (ref "J7") (pin "1") (pinfunction "NC_1") (pintype "bidirectional"))
    )
    (net (code "72") (name "unconnected-(J7-NC-Pad15)") (class "Default")
      (node (ref "J7") (pin "15") (pinfunction "NC_15") (pintype "bidirectional"))
    )
    (net (code "73") (name "unconnected-(J7-NC-Pad17)") (class "Default")
      (node (ref "J7") (pin "17") (pinfunction "NC_17") (pintype "bidirectional"))
    )
    (net (code "74") (name "unconnected-(J7-NC-Pad19)") (class "Default")
      (node (ref "J7") (pin "19") (pinfunction "NC_19") (pintype "bidirectional"))
    )
    (net (code "75") (name "unconnected-(J7-NC-Pad21)") (class "Default")
      (node (ref "J7") (pin "21") (pinfunction "NC_21") (pintype "bidirectional"))
    )
    (net (code "76") (name "unconnected-(J7-NC-Pad23)") (class "Default")
      (node (ref "J7") (pin "23") (pinfunction "NC_23") (pintype "bidirectional"))
    )
    (net (code "77") (name "unconnected-(J7-NC-Pad32)") (class "Default")
      (node (ref "J7") (pin "32") (pinfunction "NC_32") (pintype "bidirectional"))
    )
    (net (code "78") (name "unconnected-(J7-NC-Pad34)") (class "Default")
      (node (ref "J7") (pin "34") (pinfunction "NC_34") (pintype "bidirectional"))
    )
    (net (code "79") (name "unconnected-(J7-NC-Pad35)") (class "Default")
      (node (ref "J7") (pin "35") (pinfunction "NC_35") (pintype "bidirectional"))
    )
    (net (code "80") (name "unconnected-(J7-NC-Pad36)") (class "Default")
      (node (ref "J7") (pin "36") (pinfunction "NC_36") (pintype "bidirectional"))
    )
    (net (code "81") (name "unconnected-(J7-NC-Pad37)") (class "Default")
      (node (ref "J7") (pin "37") (pinfunction "NC_37") (pintype "bidirectional"))
    )
    (net (code "82") (name "unconnected-(J7-NC-Pad41)") (class "Default")
      (node (ref "J7") (pin "41") (pinfunction "NC_41") (pintype "bidirectional"))
    )
    (net (code "83") (name "unconnected-(J7-NC-Pad43)") (class "Default")
      (node (ref "J7") (pin "43") (pinfunction "NC_43") (pintype "bidirectional"))
    )
    (net (code "84") (name "unconnected-(J7-NC-Pad44)") (class "Default")
      (node (ref "J7") (pin "44") (pinfunction "NC_44") (pintype "bidirectional"))
    )
    (net (code "85") (name "unconnected-(J7-NC-Pad47)") (class "Default")
      (node (ref "J7") (pin "47") (pinfunction "NC_47") (pintype "bidirectional"))
    )
    (net (code "86") (name "unconnected-(J7-NC-Pad49)") (class "Default")
      (node (ref "J7") (pin "49") (pinfunction "NC_49") (pintype "bidirectional"))
    )
    (net (code "87") (name "unconnected-(J7-NC-Pad53)") (class "Default")
      (node (ref "J7") (pin "53") (pinfunction "NC_53") (pintype "bidirectional"))
    )
    (net (code "88") (name "unconnected-(J7-NC-Pad55)") (class "Default")
      (node (ref "J7") (pin "55") (pinfunction "NC_55") (pintype "bidirectional"))
    )
    (net (code "89") (name "unconnected-(J7-NC-Pad59)") (class "Default")
      (node (ref "J7") (pin "59") (pinfunction "NC_59") (pintype "bidirectional"))
    )
    (net (code "90") (name "unconnected-(J7-NC-Pad61)") (class "Default")
      (node (ref "J7") (pin "61") (pinfunction "NC_61") (pintype "bidirectional"))
    )
    (net (code "91") (name "unconnected-(J7-NC-Pad63)") (class "Default")
      (node (ref "J7") (pin "63") (pinfunction "NC_63") (pintype "bidirectional"))
    )
    (net (code "92") (name "unconnected-(J7-NC-Pad65)") (class "Default")
      (node (ref "J7") (pin "65") (pinfunction "NC_65") (pintype "bidirectional"))
    )
    (net (code "93") (name "unconnected-(J7-NC-Pad66)") (class "Default")
      (node (ref "J7") (pin "66") (pinfunction "NC_66") (pintype "bidirectional"))
    )
    (net (code "94") (name "unconnected-(J7-NC-Pad68)") (class "Default")
      (node (ref "J7") (pin "68") (pinfunction "NC_68") (pintype "bidirectional"))
    )
    (net (code "95") (name "unconnected-(J7-NC-Pad69)") (class "Default")
      (node (ref "J7") (pin "69") (pinfunction "NC_69") (pintype "bidirectional"))
    )
    (net (code "96") (name "unconnected-(J7-NC-Pad75)") (class "Default")
      (node (ref "J7") (pin "75") (pinfunction "NC_75") (pintype "bidirectional"))
    )
    (net (code "97") (name "unconnected-(J7-SIM_CLK-Pad14)") (class "Default")
      (node (ref "J7") (pin "14") (pinfunction "SIM_CLK_14") (pintype "bidirectional"))
    )
    (net (code "98") (name "unconnected-(J7-SIM_IO-Pad12)") (class "Default")
      (node (ref "J7") (pin "12") (pinfunction "SIM_IO_12") (pintype "bidirectional"))
    )
    (net (code "99") (name "unconnected-(J7-SIM_PRES-Pad16)") (class "Default")
      (node (ref "J7") (pin "16") (pinfunction "SIM_PRES_16") (pintype "bidirectional"))
    )
    (net (code "100") (name "unconnected-(J7-SIM_RST-Pad10)") (class "Default")
      (node (ref "J7") (pin "10") (pinfunction "SIM_RST_10") (pintype "bidirectional"))
    )
    (net (code "101") (name "unconnected-(J7-SIM_VCC-Pad8)") (class "Default")
      (node (ref "J7") (pin "8") (pinfunction "SIM_VCC_8") (pintype "bidirectional"))
    )
    (net (code "102") (name "unconnected-(J7-UDB_DM-Pad9)") (class "Default")
      (node (ref "J7") (pin "9") (pinfunction "UDB_DM_9") (pintype "bidirectional"))
    )
    (net (code "103") (name "unconnected-(J7-USB_DP-Pad7)") (class "Default")
      (node (ref "J7") (pin "7") (pinfunction "USB_DP_7") (pintype "bidirectional"))
    )
    (net (code "104") (name "unconnected-(J7-VUSB-Pad13)") (class "Default")
      (node (ref "J7") (pin "13") (pinfunction "VUSB_13") (pintype "bidirectional"))
    )
    (net (code "105") (name "unconnected-(J9-SBU1-Pad10)") (class "Default")
      (node (ref "J9") (pin "10") (pinfunction "SBU1_10") (pintype "passive"))
    )
    (net (code "106") (name "unconnected-(J9-SBU2-Pad4)") (class "Default")
      (node (ref "J9") (pin "4") (pinfunction "SBU2_4") (pintype "passive"))
    )
    (net (code "107") (name "unconnected-(U$1-NC-Pad2)") (class "Default")
      (node (ref "U$1") (pin "2") (pinfunction "NC_2") (pintype "bidirectional"))
    )
    (net (code "108") (name "unconnected-(U$1-NC2-Pad5)") (class "Default")
      (node (ref "U$1") (pin "5") (pinfunction "NC2_5") (pintype "bidirectional"))
    )
    (net (code "109") (name "unconnected-(U$1-NC3-Pad8)") (class "Default")
      (node (ref "U$1") (pin "8") (pinfunction "NC3_8") (pintype "bidirectional"))
    )
    (net (code "110") (name "unconnected-(U$1-NC4-Pad16)") (class "Default")
      (node (ref "U$1") (pin "16") (pinfunction "NC4_16") (pintype "bidirectional"))
    )
    (net (code "111") (name "unconnected-(U$1-NC5-Pad13)") (class "Default")
      (node (ref "U$1") (pin "13") (pinfunction "NC5_13") (pintype "bidirectional"))
    )
    (net (code "112") (name "unconnected-(U$1-NC6-Pad10)") (class "Default")
      (node (ref "U$1") (pin "10") (pinfunction "NC6_10") (pintype "bidirectional"))
    )
    (net (code "113") (name "unconnected-(U1-GPIO8-Pad11)") (class "Default")
      (node (ref "U1") (pin "11") (pinfunction "GPIO8_11") (pintype "bidirectional"))
    )
    (net (code "114") (name "unconnected-(U1-GPIO9-Pad12)") (class "Default")
      (node (ref "U1") (pin "12") (pinfunction "GPIO9_12") (pintype "bidirectional"))
    )
    (net (code "115") (name "unconnected-(U1-GPIO10-Pad13)") (class "Default")
      (node (ref "U1") (pin "13") (pinfunction "GPIO10_13") (pintype "bidirectional"))
    )
    (net (code "116") (name "unconnected-(U1-GPIO11-Pad14)") (class "Default")
      (node (ref "U1") (pin "14") (pinfunction "GPIO11_14") (pintype "bidirectional"))
    )
    (net (code "117") (name "unconnected-(U1-GPIO12-Pad15)") (class "Default")
      (node (ref "U1") (pin "15") (pinfunction "GPIO12_15") (pintype "bidirectional"))
    )
    (net (code "118") (name "unconnected-(U1-GPIO13-Pad16)") (class "Default")
      (node (ref "U1") (pin "16") (pinfunction "GPIO13_16") (pintype "bidirectional"))
    )
    (net (code "119") (name "unconnected-(U1-GPIO14-Pad17)") (class "Default")
      (node (ref "U1") (pin "17") (pinfunction "GPIO14_17") (pintype "bidirectional"))
    )
    (net (code "120") (name "unconnected-(U1-GPIO15-Pad18)") (class "Default")
      (node (ref "U1") (pin "18") (pinfunction "GPIO15_18") (pintype "bidirectional"))
    )
    (net (code "121") (name "unconnected-(U1-GPIO26{slash}ADC0-Pad38)") (class "Default")
      (node (ref "U1") (pin "38") (pinfunction "GPIO26/ADC0_38") (pintype "bidirectional"))
    )
    (net (code "122") (name "unconnected-(U1-GPIO27{slash}ADC1-Pad39)") (class "Default")
      (node (ref "U1") (pin "39") (pinfunction "GPIO27/ADC1_39") (pintype "bidirectional"))
    )
    (net (code "123") (name "unconnected-(U1-GPIO28{slash}ADC2-Pad40)") (class "Default")
      (node (ref "U1") (pin "40") (pinfunction "GPIO28/ADC2_40") (pintype "bidirectional"))
    )
    (net (code "124") (name "unconnected-(U1-GPIO29{slash}ADC3-Pad41)") (class "Default")
      (node (ref "U1") (pin "41") (pinfunction "GPIO29/ADC3_41") (pintype "bidirectional"))
    )
    (net (code "125") (name "unconnected-(U5-ASCX-Pad3)") (class "Default")
      (node (ref "U5") (pin "3") (pinfunction "ASCX_3") (pintype "bidirectional"))
    )
    (net (code "126") (name "unconnected-(U5-ASDX-Pad2)") (class "Default")
      (node (ref "U5") (pin "2") (pinfunction "ASDX_2") (pintype "bidirectional"))
    )
    (net (code "127") (name "unconnected-(U5-OSCB-Pad10)") (class "Default")
      (node (ref "U5") (pin "10") (pinfunction "OSCB_10") (pintype "input"))
    )
    (net (code "128") (name "unconnected-(U5-OSDO-Pad11)") (class "Default")
      (node (ref "U5") (pin "11") (pinfunction "OSDO_11") (pintype "output"))
    )
    (net (code "129") (name "~{RESET}") (class "Default")
      (node (ref "S2") (pin "1") (pinfunction "1_1") (pintype "passive"))
      (node (ref "U1") (pin "26") (pinfunction "RUN_26") (pintype "input"))
    )
  )
)
